# boxer_main.net
KiCad netlist of a schematic drawn in Altium Designer
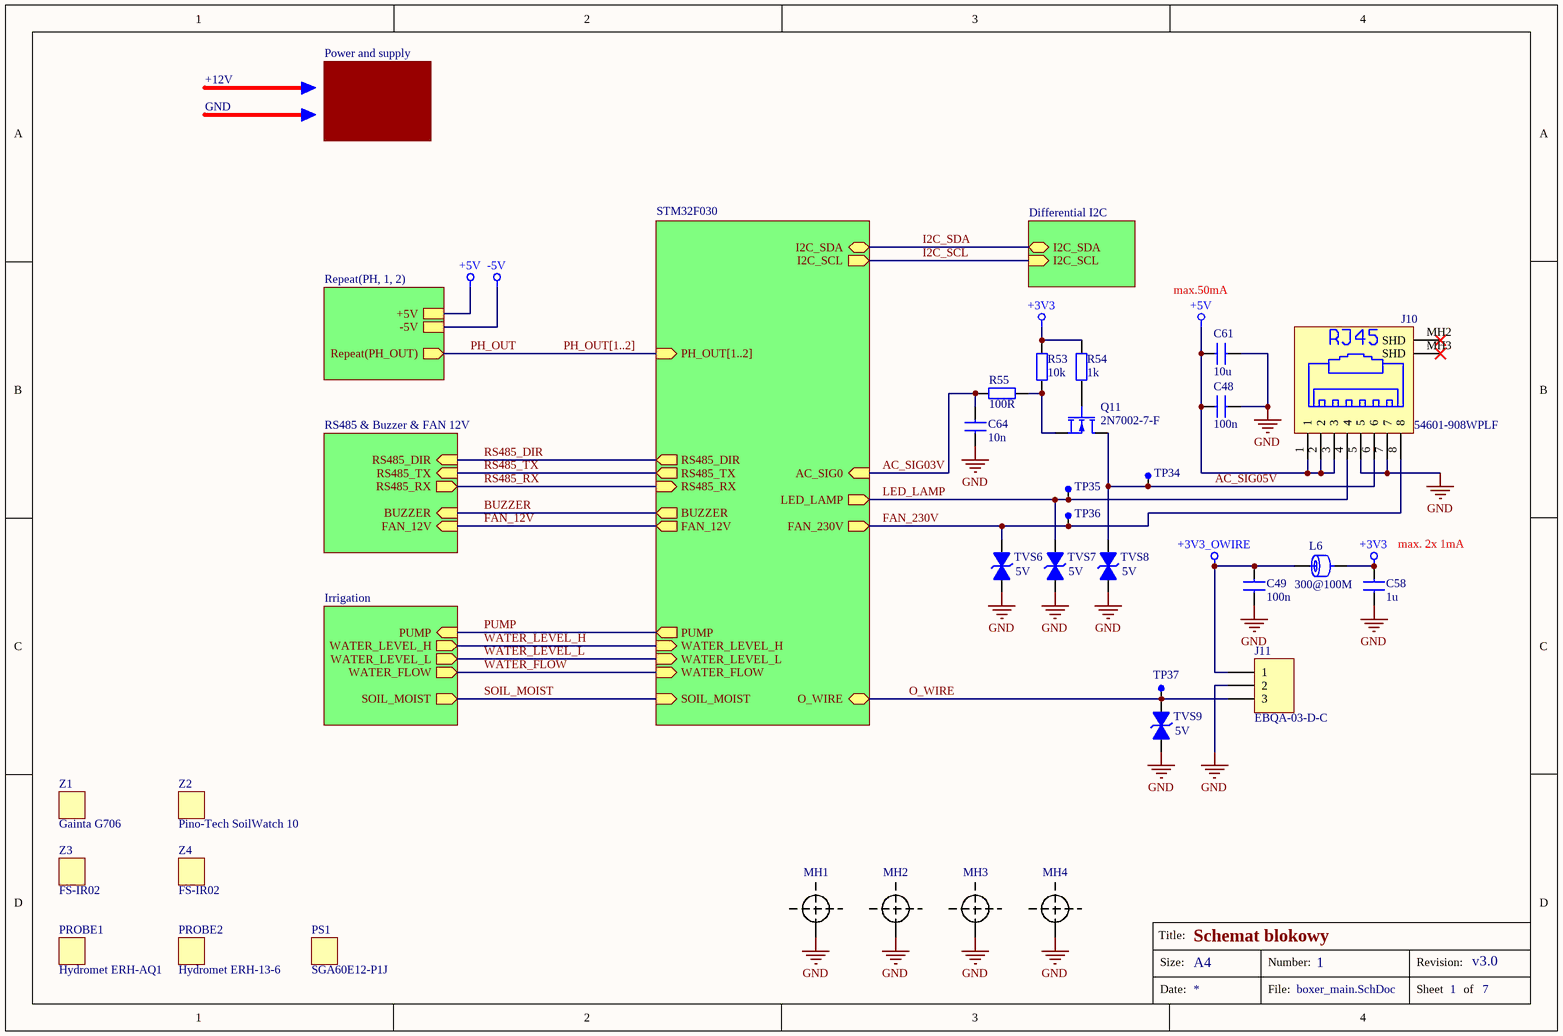
[diagram p0: boxer_main.SchDoc]

(export (version "E")
  (design (tool "Eeschema 10.0.6"))
  (components
    (comp (ref "C48")
      (value "100n")
      (footprint "C_0805")
      (description "Capacitor")
      (libsource (lib "boxer_pas") (part "Capacitor"))
    )
    (comp (ref "C49")
      (value "100n")
      (footprint "C_0805")
      (description "Capacitor")
      (libsource (lib "boxer_pas") (part "Capacitor"))
    )
    (comp (ref "C58")
      (value "1u")
      (footprint "C_0805")
      (description "Capacitor")
      (fields (field (name "Comment") "C0805C105K4RACAUTO"))
      (libsource (lib "boxer_pas") (part "Capacitor"))
    )
    (comp (ref "C61")
      (value "10u")
      (footprint "C_1206")
      (description "Capacitor")
      (libsource (lib "boxer_pas") (part "Capacitor"))
    )
    (comp (ref "C64")
      (value "10n")
      (footprint "C_0805")
      (description "Capacitor")
      (libsource (lib "boxer_pas") (part "Capacitor"))
    )
    (comp (ref "J10")
      (value "54601-908WPLF")
      (footprint "RJ45_54601-908WPLF")
      (description "RJ45 Socket, 8pin, No Key, Molex MX-95001-2881")
      (libsource (lib "boxer_mechanical") (part "RJ45-8"))
    )
    (comp (ref "J11")
      (value "EBQA-03-D-C")
      (footprint "284512-3")
      (description "Header, 3-Pin")
      (libsource (lib "boxer_mechanical") (part "Header 3"))
    )
    (comp (ref "L6")
      (value "300@100M")
      (footprint "L_0805")
      (description "Ferrite Bead")
      (fields (field (name "Comment") "742792031"))
      (libsource (lib "boxer_pas") (part "FB"))
    )
    (comp (ref "MH1")
      (value "Mounting hole")
      (footprint "MH_M2.5")
      (description "Mounting hole 2.3mm")
      (libsource (lib "boxer_mechanical") (part "Mounting hole"))
    )
    (comp (ref "MH2")
      (value "Mounting hole")
      (footprint "MH_M2.5")
      (description "Mounting hole 2.3mm")
      (libsource (lib "boxer_mechanical") (part "Mounting hole"))
    )
    (comp (ref "MH3")
      (value "Mounting hole")
      (footprint "MH_M2.5")
      (description "Mounting hole 2.3mm")
      (libsource (lib "boxer_mechanical") (part "Mounting hole"))
    )
    (comp (ref "MH4")
      (value "Mounting hole")
      (footprint "MH_M2.5")
      (description "Mounting hole 2.3mm")
      (libsource (lib "boxer_mechanical") (part "Mounting hole"))
    )
    (comp (ref "PROBE1")
      (value "Hydromet ERH-AQ1")
      (description "Hydromet ERH-AQ1 Water pH probe")
      (libsource (lib "boxer_mechanical") (part "ERH-AQ1"))
    )
    (comp (ref "PROBE2")
      (value "Hydromet ERH-13-6")
      (description "Hydromet ERH-AQ1 Soil pH probe")
      (libsource (lib "boxer_mechanical") (part "ERH-13-6"))
    )
    (comp (ref "PS1") (value "SGA60E12-P1J") (libsource (lib "boxer_mechanical") (part "EPS-45-12")))
    (comp (ref "Q11")
      (value "2N7002-7-F")
      (footprint "SOT-23")
      (description "N-Channel MOSFET")
      (libsource (lib "boxer_pas") (part "MOSFET-N"))
    )
    (comp (ref "R53")
      (value "10k")
      (footprint "R_1206")
      (description "Resistor")
      (libsource (lib "") (part "Resistor_1"))
    )
    (comp (ref "R54")
      (value "1k")
      (footprint "R_0805")
      (description "Resistor")
      (libsource (lib "") (part "Resistor_1"))
    )
    (comp (ref "R55")
      (value "100R")
      (footprint "R_0805")
      (description "Resistor")
      (libsource (lib "boxer_pas") (part "Resistor"))
    )
    (comp (ref "TP34")
      (value "TEST PAD")
      (footprint "PIN")
      (libsource (lib "boxer_mechanical") (part "TEST_PAD"))
    )
    (comp (ref "TP35")
      (value "TEST PAD")
      (footprint "PIN")
      (libsource (lib "boxer_mechanical") (part "TEST_PAD"))
    )
    (comp (ref "TP36")
      (value "TEST PAD")
      (footprint "PIN")
      (libsource (lib "boxer_mechanical") (part "TEST_PAD"))
    )
    (comp (ref "TP37")
      (value "TEST PAD")
      (footprint "PIN")
      (libsource (lib "boxer_mechanical") (part "TEST_PAD"))
    )
    (comp (ref "TVS6")
      (value "5V")
      (footprint "D_SMA")
      (description "Transil")
      (fields (field (name "Comment") "SMAJ5.0ALFCT-ND"))
      (libsource (lib "boxer_pas") (part "Transil"))
    )
    (comp (ref "TVS7")
      (value "5V")
      (footprint "D_SMA")
      (description "Transil")
      (fields (field (name "Comment") "SMAJ5.0ALFCT-ND"))
      (libsource (lib "boxer_pas") (part "Transil"))
    )
    (comp (ref "TVS8")
      (value "5V")
      (footprint "D_SMA")
      (description "Transil")
      (fields (field (name "Comment") "SMAJ5.0ALFCT-ND"))
      (libsource (lib "boxer_pas") (part "Transil"))
    )
    (comp (ref "TVS9")
      (value "5V")
      (footprint "D_SMA")
      (description "Transil")
      (fields (field (name "Comment") "SMAJ5.0ALFCT-ND"))
      (libsource (lib "boxer_pas") (part "Transil"))
    )
    (comp (ref "Z1")
      (value "Gainta G706")
      (footprint "Gainta G706")
      (libsource (lib "boxer_mechanical") (part "ENCLOSURE"))
    )
    (comp (ref "Z2")
      (value "Pino-Tech SoilWatch 10")
      (libsource (lib "boxer_mechanical") (part "SoilWatch10"))
    )
    (comp (ref "Z3")
      (value "FS-IR02")
      (description "IR Liquid Level Sensor, Vcc 5VDC; Iout = 12mA; Temp. = -25*C - 105*C")
      (libsource (lib "boxer_mechanical") (part "FS-IR02"))
    )
    (comp (ref "Z4")
      (value "FS-IR02")
      (description "IR Liquid Level Sensor, Vcc 5VDC; Iout = 12mA; Temp. = -25*C - 105*C")
      (libsource (lib "boxer_mechanical") (part "FS-IR02"))
    )
  )
  (nets
    (net (code "3") (name "+3V3") (class "Default")
      (node (ref "C58") (pin "2") (pinfunction "2_2") (pintype "passive"))
      (node (ref "L6") (pin "2") (pinfunction "2_2") (pintype "passive"))
      (node (ref "R53") (pin "2") (pinfunction "2_2") (pintype "passive"))
      (node (ref "R54") (pin "2") (pinfunction "2_2") (pintype "passive"))
    )
    (net (code "4") (name "+3V3_OWIRE") (class "Default")
      (node (ref "C49") (pin "1") (pinfunction "1_1") (pintype "passive"))
      (node (ref "J11") (pin "1") (pinfunction "1_1") (pintype "passive"))
      (node (ref "L6") (pin "1") (pinfunction "1_1") (pintype "passive"))
    )
    (net (code "5") (name "+5V") (class "Default")
      (node (ref "C48") (pin "2") (pinfunction "2_2") (pintype "passive"))
      (node (ref "C61") (pin "2") (pinfunction "2_2") (pintype "passive"))
      (node (ref "J10") (pin "1") (pinfunction "1_1") (pintype "passive"))
      (node (ref "J10") (pin "2") (pinfunction "2_2") (pintype "passive"))
      (node (ref "J10") (pin "3") (pinfunction "3_3") (pintype "passive"))
    )
    (net (code "7") (name "/AC_SIG03V") (class "Default")
      (node (ref "C64") (pin "1") (pinfunction "1_1") (pintype "passive"))
      (node (ref "R55") (pin "2") (pinfunction "2_2") (pintype "passive"))
    )
    (net (code "8") (name "/AC_SIG05V") (class "Default")
      (node (ref "J10") (pin "6") (pinfunction "6_6") (pintype "passive"))
      (node (ref "Q11") (pin "3") (pinfunction "D_3") (pintype "passive"))
      (node (ref "TP34") (pin "1") (pinfunction "1_1") (pintype "passive"))
      (node (ref "TVS8") (pin "2") (pinfunction "K_2") (pintype "passive"))
    )
    (net (code "11") (name "/FAN_230V") (class "Default")
      (node (ref "J10") (pin "8") (pinfunction "8_8") (pintype "passive"))
      (node (ref "TP36") (pin "1") (pinfunction "1_1") (pintype "passive"))
      (node (ref "TVS6") (pin "2") (pinfunction "K_2") (pintype "passive"))
    )
    (net (code "14") (name "/LED_LAMP") (class "Default")
      (node (ref "J10") (pin "4") (pinfunction "4_4") (pintype "passive"))
      (node (ref "TP35") (pin "1") (pinfunction "1_1") (pintype "passive"))
      (node (ref "TVS7") (pin "2") (pinfunction "K_2") (pintype "passive"))
    )
    (net (code "15") (name "/O_WIRE") (class "Default")
      (node (ref "J11") (pin "3") (pinfunction "3_3") (pintype "passive"))
      (node (ref "TP37") (pin "1") (pinfunction "1_1") (pintype "passive"))
      (node (ref "TVS9") (pin "2") (pinfunction "K_2") (pintype "passive"))
    )
    (net (code "26") (name "GND") (class "Default")
      (node (ref "C48") (pin "1") (pinfunction "1_1") (pintype "passive"))
      (node (ref "C49") (pin "2") (pinfunction "2_2") (pintype "passive"))
      (node (ref "C58") (pin "1") (pinfunction "1_1") (pintype "passive"))
      (node (ref "C61") (pin "1") (pinfunction "1_1") (pintype "passive"))
      (node (ref "C64") (pin "2") (pinfunction "2_2") (pintype "passive"))
      (node (ref "J10") (pin "5") (pinfunction "5_5") (pintype "passive"))
      (node (ref "J10") (pin "7") (pinfunction "7_7") (pintype "passive"))
      (node (ref "J11") (pin "2") (pinfunction "2_2") (pintype "passive"))
      (node (ref "MH1") (pin "MH") (pinfunction "MH_MH") (pintype "passive"))
      (node (ref "MH2") (pin "MH") (pinfunction "MH_MH") (pintype "passive"))
      (node (ref "MH3") (pin "MH") (pinfunction "MH_MH") (pintype "passive"))
      (node (ref "MH4") (pin "MH") (pinfunction "MH_MH") (pintype "passive"))
      (node (ref "TVS6") (pin "1") (pinfunction "A_1") (pintype "passive"))
      (node (ref "TVS7") (pin "1") (pinfunction "A_1") (pintype "passive"))
      (node (ref "TVS8") (pin "1") (pinfunction "A_1") (pintype "passive"))
      (node (ref "TVS9") (pin "1") (pinfunction "A_1") (pintype "passive"))
    )
    (net (code "27") (name "Net-(Q11-G)") (class "Default")
      (node (ref "Q11") (pin "1") (pinfunction "G_1") (pintype "passive"))
      (node (ref "R54") (pin "1") (pinfunction "1_1") (pintype "passive"))
    )
    (net (code "28") (name "Net-(Q11-S)") (class "Default")
      (node (ref "Q11") (pin "2") (pinfunction "S_2") (pintype "passive"))
      (node (ref "R53") (pin "1") (pinfunction "1_1") (pintype "passive"))
      (node (ref "R55") (pin "1") (pinfunction "1_1") (pintype "passive"))
    )
    (net (code "29") (name "unconnected-(J10-SHD-PadMH2)") (class "Default")
      (node (ref "J10") (pin "MH2") (pinfunction "SHD_MH2") (pintype "passive+no_connect"))
    )
    (net (code "30") (name "unconnected-(J10-SHD-PadMH3)") (class "Default")
      (node (ref "J10") (pin "MH3") (pinfunction "SHD_MH3") (pintype "passive+no_connect"))
    )
  )
)
